# Project-PowerSwitch001.net
KiCad netlist of a schematic drawn in EAGLE
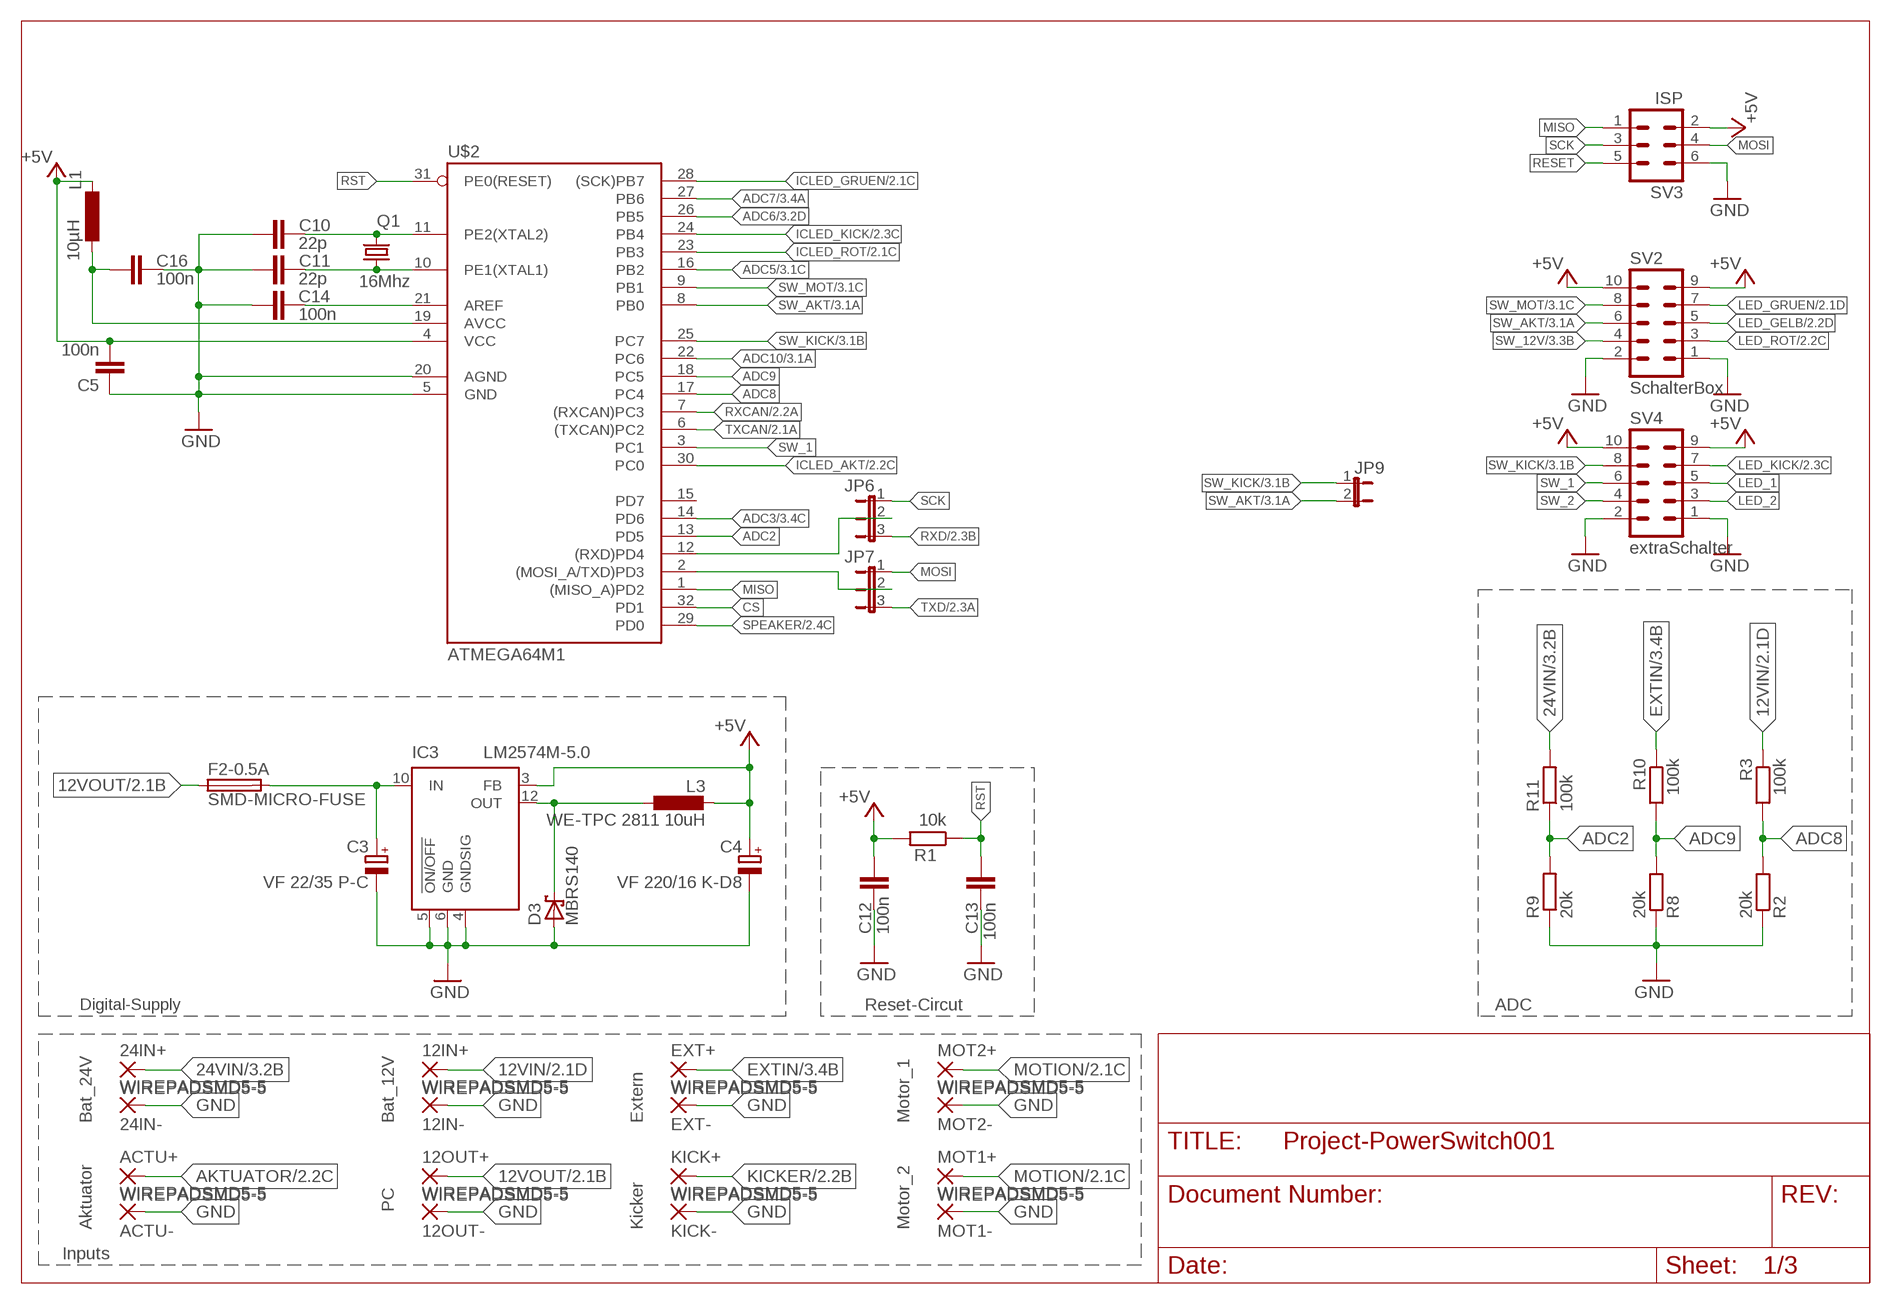
[diagram p0: schematic, sheet 1]
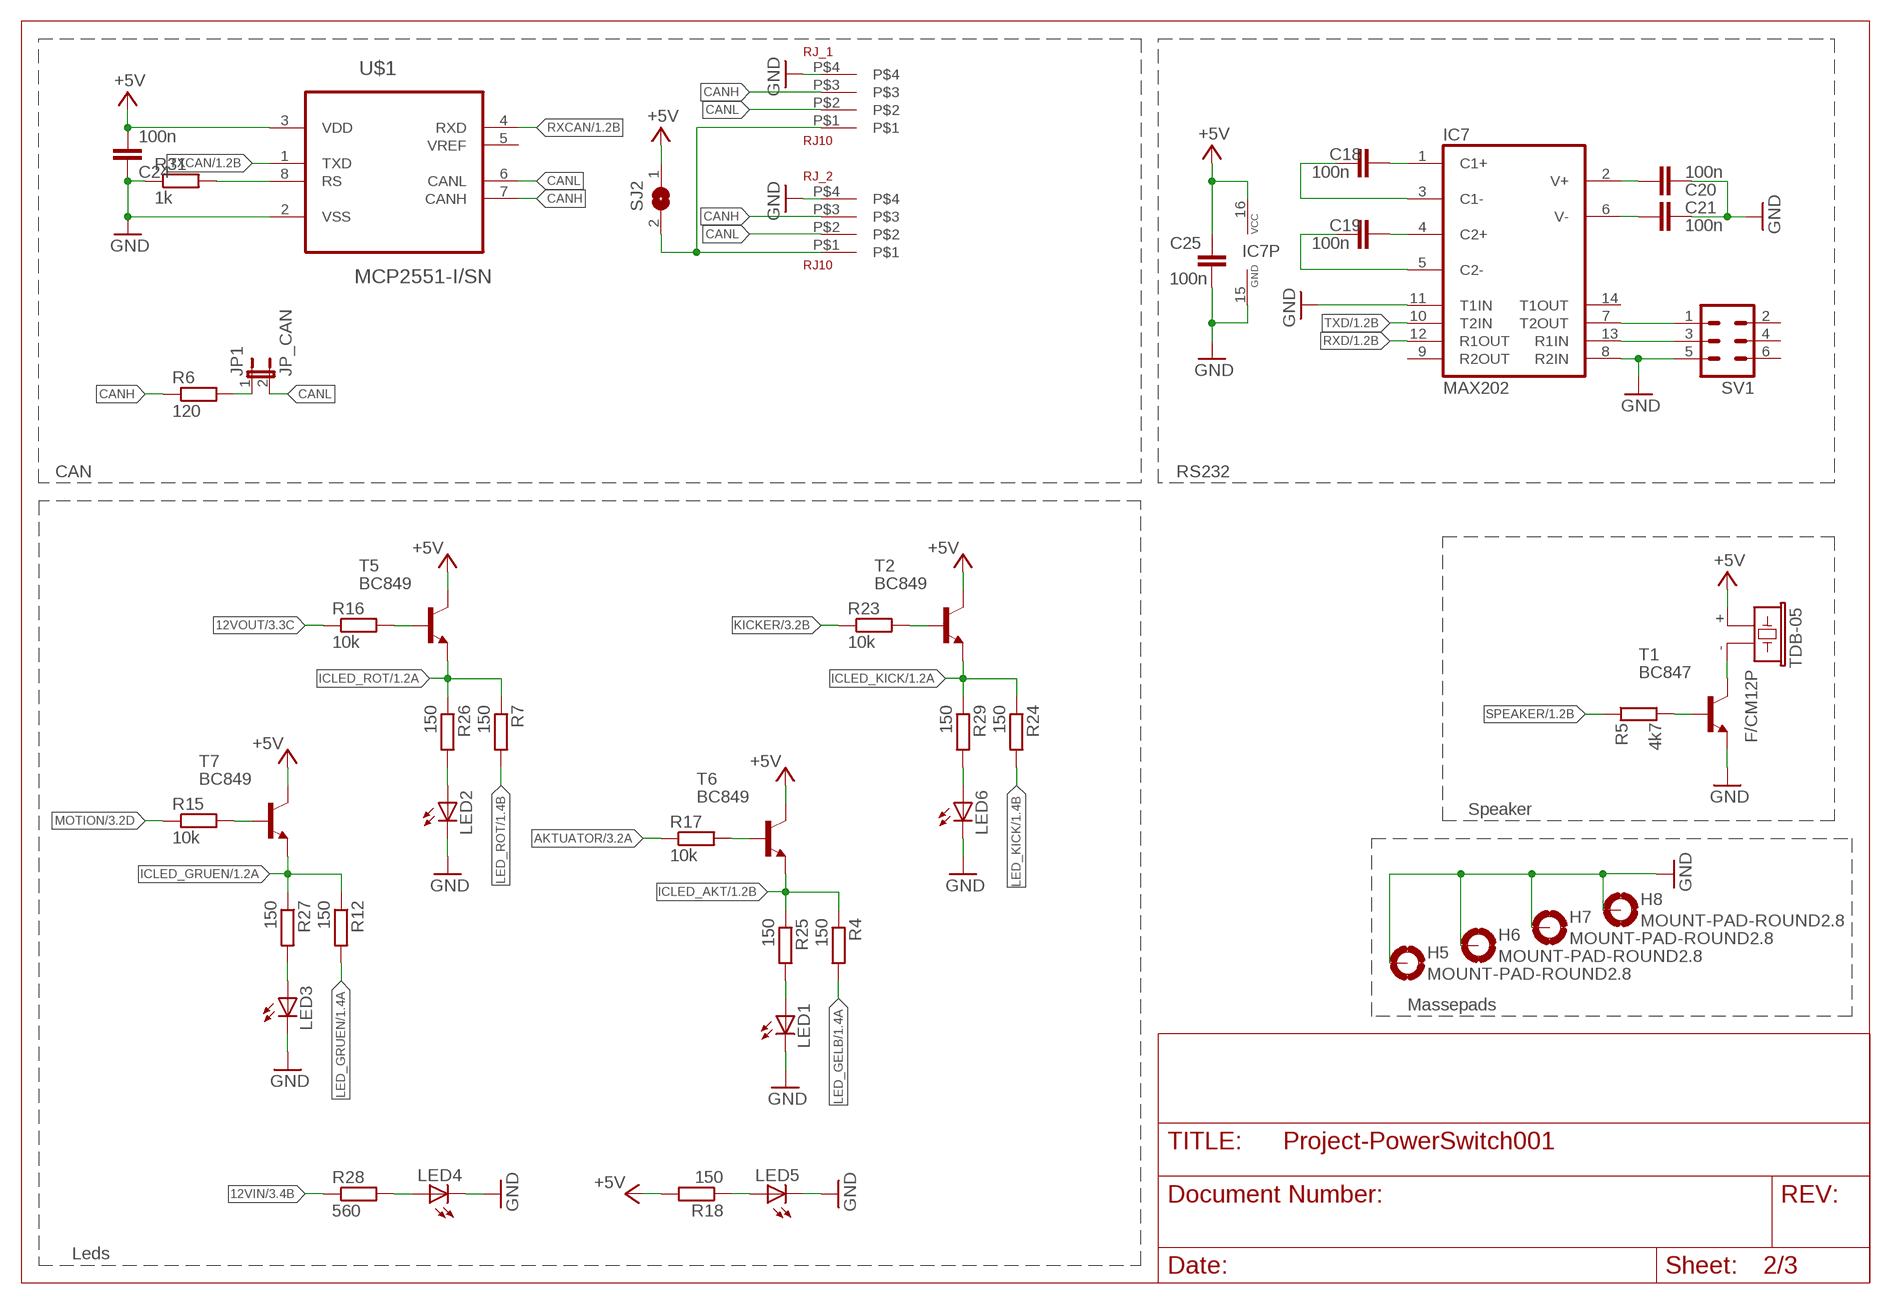
[diagram p1: schematic, sheet 2]
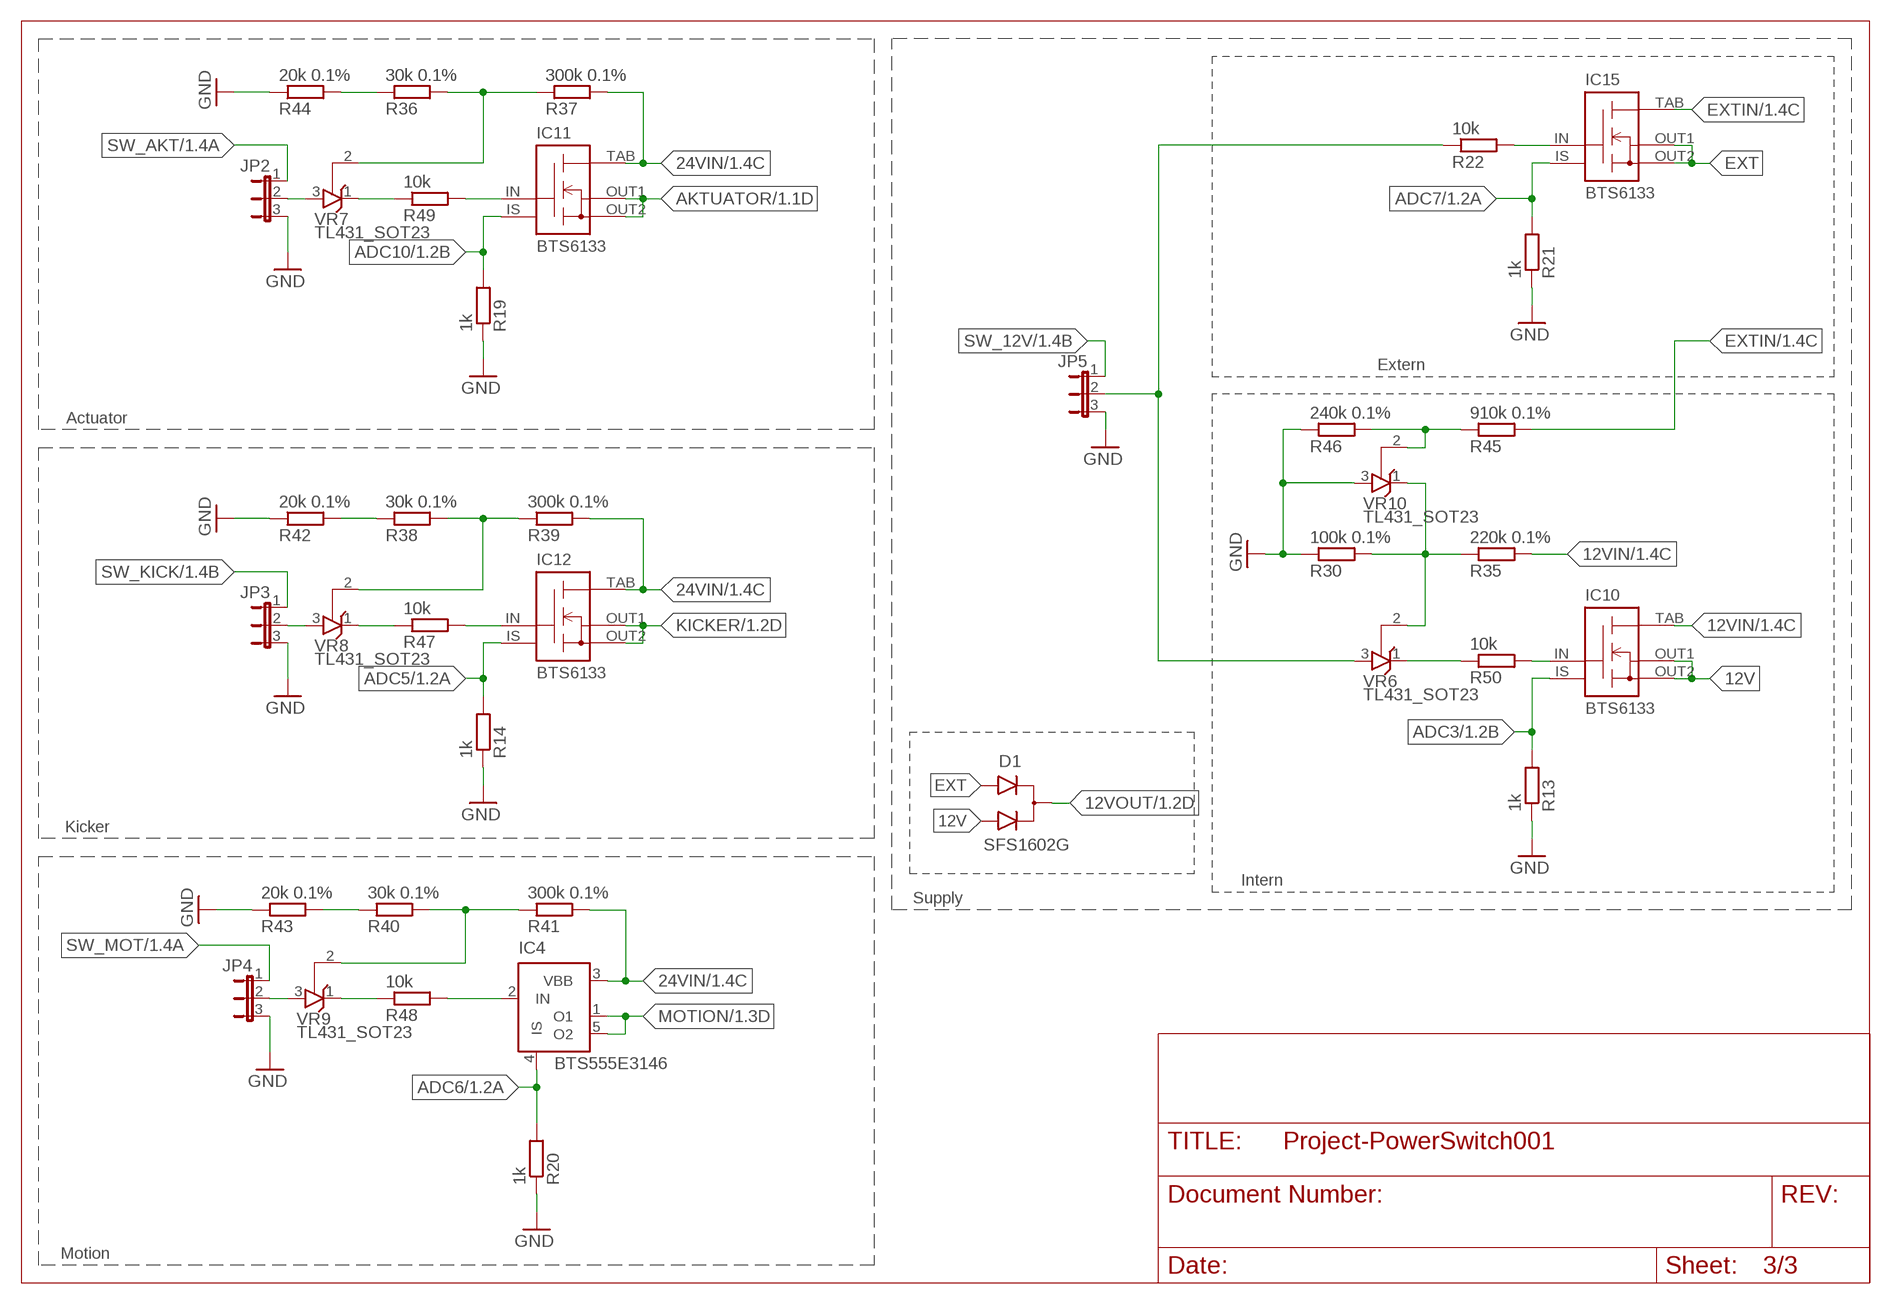
[diagram p2: schematic, sheet 3]

(export (version "E")
  (design (tool "Eeschema 10.0.6"))
  (components
    (comp (ref "C18")
      (value "100n")
      (footprint "eagle-import:C0603K")
      (libsource (lib "eagle-import") (part "C-EUC0603K"))
    )
    (comp (ref "C19")
      (value "100n")
      (footprint "eagle-import:C0603K")
      (libsource (lib "eagle-import") (part "C-EUC0603K"))
    )
    (comp (ref "C20")
      (value "100n")
      (footprint "eagle-import:C0603K")
      (libsource (lib "eagle-import") (part "C-EUC0603K"))
    )
    (comp (ref "C21")
      (value "100n")
      (footprint "eagle-import:C0603K")
      (libsource (lib "eagle-import") (part "C-EUC0603K"))
    )
    (comp (ref "C24")
      (value "100n")
      (footprint "eagle-import:C0603")
      (libsource (lib "eagle-import") (part "C-EUC0603"))
    )
    (comp (ref "C25")
      (value "100n")
      (footprint "eagle-import:C0603K")
      (libsource (lib "eagle-import") (part "C-EUC0603K"))
    )
    (comp (ref "H5")
      (value "MOUNT-PAD-ROUND2.8")
      (footprint "eagle-import:2,8-PAD")
      (libsource (lib "eagle-import") (part "MOUNT-PAD-ROUND2.8"))
    )
    (comp (ref "H6")
      (value "MOUNT-PAD-ROUND2.8")
      (footprint "eagle-import:2,8-PAD")
      (libsource (lib "eagle-import") (part "MOUNT-PAD-ROUND2.8"))
    )
    (comp (ref "H7")
      (value "MOUNT-PAD-ROUND2.8")
      (footprint "eagle-import:2,8-PAD")
      (libsource (lib "eagle-import") (part "MOUNT-PAD-ROUND2.8"))
    )
    (comp (ref "H8")
      (value "MOUNT-PAD-ROUND2.8")
      (footprint "eagle-import:2,8-PAD")
      (libsource (lib "eagle-import") (part "MOUNT-PAD-ROUND2.8"))
    )
    (comp (ref "IC7")
      (value "MAX202")
      (footprint "eagle-import:SO16")
      (fields (field (name "MPN") "MAX3232CSE"))
      (libsource (lib "eagle-import") (part "MAX3232SEC"))
    )
    (comp (ref "JP1")
      (value "JP_CAN")
      (footprint "eagle-import:JP1")
      (libsource (lib "eagle-import") (part "JP1E"))
    )
    (comp (ref "LED1")
      (value "LEDCHIPLED_0805")
      (footprint "eagle-import:CHIPLED_0805")
      (libsource (lib "eagle-import") (part "LEDCHIPLED_0805"))
    )
    (comp (ref "LED2")
      (value "LEDCHIPLED_0805")
      (footprint "eagle-import:CHIPLED_0805")
      (libsource (lib "eagle-import") (part "LEDCHIPLED_0805"))
    )
    (comp (ref "LED3")
      (value "LEDCHIPLED_0805")
      (footprint "eagle-import:CHIPLED_0805")
      (libsource (lib "eagle-import") (part "LEDCHIPLED_0805"))
    )
    (comp (ref "LED4")
      (value "LEDCHIPLED_0805")
      (footprint "eagle-import:CHIPLED_0805")
      (libsource (lib "eagle-import") (part "LEDCHIPLED_0805"))
    )
    (comp (ref "LED5")
      (value "LEDCHIPLED_0805")
      (footprint "eagle-import:CHIPLED_0805")
      (libsource (lib "eagle-import") (part "LEDCHIPLED_0805"))
    )
    (comp (ref "LED6")
      (value "LEDCHIPLED_0805")
      (footprint "eagle-import:CHIPLED_0805")
      (libsource (lib "eagle-import") (part "LEDCHIPLED_0805"))
    )
    (comp (ref "R4")
      (value "150")
      (footprint "eagle-import:R0805")
      (libsource (lib "eagle-import") (part "R-EU_R0805"))
    )
    (comp (ref "R5")
      (value "4k7")
      (footprint "eagle-import:R0805")
      (libsource (lib "eagle-import") (part "R-EU_R0805"))
    )
    (comp (ref "R6")
      (value "120")
      (footprint "eagle-import:M0805")
      (libsource (lib "eagle-import") (part "R-EU_M0805"))
    )
    (comp (ref "R7")
      (value "150")
      (footprint "eagle-import:R0805")
      (libsource (lib "eagle-import") (part "R-EU_R0805"))
    )
    (comp (ref "R12")
      (value "150")
      (footprint "eagle-import:R0805")
      (libsource (lib "eagle-import") (part "R-EU_R0805"))
    )
    (comp (ref "R15")
      (value "10k")
      (footprint "eagle-import:R0805")
      (libsource (lib "eagle-import") (part "R-EU_R0805"))
    )
    (comp (ref "R16")
      (value "10k")
      (footprint "eagle-import:R0805")
      (libsource (lib "eagle-import") (part "R-EU_R0805"))
    )
    (comp (ref "R17")
      (value "10k")
      (footprint "eagle-import:R0805")
      (libsource (lib "eagle-import") (part "R-EU_R0805"))
    )
    (comp (ref "R18")
      (value "150")
      (footprint "eagle-import:R0805")
      (libsource (lib "eagle-import") (part "R-EU_R0805"))
    )
    (comp (ref "R23")
      (value "10k")
      (footprint "eagle-import:R0805")
      (libsource (lib "eagle-import") (part "R-EU_R0805"))
    )
    (comp (ref "R24")
      (value "150")
      (footprint "eagle-import:R0805")
      (libsource (lib "eagle-import") (part "R-EU_R0805"))
    )
    (comp (ref "R25")
      (value "150")
      (footprint "eagle-import:R0805")
      (libsource (lib "eagle-import") (part "R-EU_R0805"))
    )
    (comp (ref "R26")
      (value "150")
      (footprint "eagle-import:R0805")
      (libsource (lib "eagle-import") (part "R-EU_R0805"))
    )
    (comp (ref "R27")
      (value "150")
      (footprint "eagle-import:R0805")
      (libsource (lib "eagle-import") (part "R-EU_R0805"))
    )
    (comp (ref "R28")
      (value "560")
      (footprint "eagle-import:R0805")
      (libsource (lib "eagle-import") (part "R-EU_R0805"))
    )
    (comp (ref "R29")
      (value "150")
      (footprint "eagle-import:R0805")
      (libsource (lib "eagle-import") (part "R-EU_R0805"))
    )
    (comp (ref "R31")
      (value "1k")
      (footprint "eagle-import:R0805")
      (libsource (lib "eagle-import") (part "R-EU_R0805"))
    )
    (comp (ref "RJ_1")
      (value "RJ10")
      (footprint "eagle-import:RJ10")
      (libsource (lib "eagle-import") (part "RJ10"))
    )
    (comp (ref "RJ_2")
      (value "RJ10")
      (footprint "eagle-import:RJ10")
      (libsource (lib "eagle-import") (part "RJ10"))
    )
    (comp (ref "SJ2") (value "SJ") (footprint "eagle-import:SJ") (libsource (lib "eagle-import") (part "SJ")))
    (comp (ref "SV1")
      (value "ML6")
      (footprint "eagle-import:ML6")
      (libsource (lib "eagle-import") (part "ML6"))
    )
    (comp (ref "T1")
      (value "BC847")
      (footprint "eagle-import:SOT23")
      (libsource (lib "eagle-import") (part "BC847"))
    )
    (comp (ref "T2")
      (value "BC849")
      (footprint "eagle-import:SOT23")
      (libsource (lib "eagle-import") (part "BC849"))
    )
    (comp (ref "T5")
      (value "BC849")
      (footprint "eagle-import:SOT23")
      (libsource (lib "eagle-import") (part "BC849"))
    )
    (comp (ref "T6")
      (value "BC849")
      (footprint "eagle-import:SOT23")
      (libsource (lib "eagle-import") (part "BC849"))
    )
    (comp (ref "T7")
      (value "BC849")
      (footprint "eagle-import:SOT23")
      (libsource (lib "eagle-import") (part "BC849"))
    )
    (comp (ref "TDB-05")
      (value "F/CM12P")
      (footprint "eagle-import:F_CM12P")
      (libsource (lib "eagle-import") (part "F/CM12P"))
    )
    (comp (ref "U$1")
      (value "MCP2551-I/SN")
      (footprint "eagle-import:SOIC127P600X175-8N")
      (libsource (lib "eagle-import") (part "MCP2551-I/SN"))
    )
    (comp (ref "12IN+")
      (value "WIREPADSMD5-5")
      (footprint "eagle-import:5-5")
      (libsource (lib "eagle-import") (part "WIREPADSMD5-5"))
    )
    (comp (ref "12IN-")
      (value "WIREPADSMD5-5")
      (footprint "eagle-import:5-5")
      (libsource (lib "eagle-import") (part "WIREPADSMD5-5"))
    )
    (comp (ref "12OUT+")
      (value "WIREPADSMD5-5")
      (footprint "eagle-import:5-5")
      (libsource (lib "eagle-import") (part "WIREPADSMD5-5"))
    )
    (comp (ref "12OUT-")
      (value "WIREPADSMD5-5")
      (footprint "eagle-import:5-5")
      (libsource (lib "eagle-import") (part "WIREPADSMD5-5"))
    )
    (comp (ref "24IN+")
      (value "WIREPADSMD5-5")
      (footprint "eagle-import:5-5")
      (libsource (lib "eagle-import") (part "WIREPADSMD5-5"))
    )
    (comp (ref "24IN-")
      (value "WIREPADSMD5-5")
      (footprint "eagle-import:5-5")
      (libsource (lib "eagle-import") (part "WIREPADSMD5-5"))
    )
    (comp (ref "ACTU+")
      (value "WIREPADSMD5-5")
      (footprint "eagle-import:5-5")
      (libsource (lib "eagle-import") (part "WIREPADSMD5-5"))
    )
    (comp (ref "ACTU-")
      (value "WIREPADSMD5-5")
      (footprint "eagle-import:5-5")
      (libsource (lib "eagle-import") (part "WIREPADSMD5-5"))
    )
    (comp (ref "C3")
      (value "VF 22/35 P-C")
      (footprint "eagle-import:PANASONIC_C")
      (libsource (lib "eagle-import") (part "CPOL-EUC"))
    )
    (comp (ref "C4")
      (value "VF 220/16 K-D8")
      (footprint "eagle-import:PANASONIC_D")
      (libsource (lib "eagle-import") (part "CPOL-EUD"))
    )
    (comp (ref "C5")
      (value "100n")
      (footprint "eagle-import:C0603K")
      (libsource (lib "eagle-import") (part "C-EUC0603K"))
    )
    (comp (ref "C10")
      (value "22p")
      (footprint "eagle-import:C0603K")
      (libsource (lib "eagle-import") (part "C-EUC0603K"))
    )
    (comp (ref "C11")
      (value "22p")
      (footprint "eagle-import:C0603K")
      (libsource (lib "eagle-import") (part "C-EUC0603K"))
    )
    (comp (ref "C12")
      (value "100n")
      (footprint "eagle-import:C0603K")
      (libsource (lib "eagle-import") (part "C-EUC0603K"))
    )
    (comp (ref "C13")
      (value "100n")
      (footprint "eagle-import:C0603K")
      (libsource (lib "eagle-import") (part "C-EUC0603K"))
    )
    (comp (ref "C14")
      (value "100n")
      (footprint "eagle-import:C0603K")
      (libsource (lib "eagle-import") (part "C-EUC0603K"))
    )
    (comp (ref "C16")
      (value "100n")
      (footprint "eagle-import:C0603K")
      (libsource (lib "eagle-import") (part "C-EUC0603K"))
    )
    (comp (ref "D3")
      (value "MBRS140")
      (footprint "eagle-import:SMB")
      (libsource (lib "eagle-import") (part "SCHOTTKY-DIODESMD"))
    )
    (comp (ref "EXT+")
      (value "WIREPADSMD5-5")
      (footprint "eagle-import:5-5")
      (libsource (lib "eagle-import") (part "WIREPADSMD5-5"))
    )
    (comp (ref "EXT-")
      (value "WIREPADSMD5-5")
      (footprint "eagle-import:5-5")
      (libsource (lib "eagle-import") (part "WIREPADSMD5-5"))
    )
    (comp (ref "F2-0.5A")
      (value "SMD-MICRO-FUSE")
      (footprint "eagle-import:SMD-6,1X2,6")
      (libsource (lib "eagle-import") (part "SMD-MICRO-FUSE"))
    )
    (comp (ref "IC3")
      (value "LM2574M-5.0")
      (footprint "eagle-import:SO14W")
      (libsource (lib "eagle-import") (part "LM2574?-M5.0"))
    )
    (comp (ref "JP6")
      (value "JP2E")
      (footprint "eagle-import:JP2")
      (libsource (lib "eagle-import") (part "JP2E"))
    )
    (comp (ref "JP7")
      (value "JP2E")
      (footprint "eagle-import:JP2")
      (libsource (lib "eagle-import") (part "JP2E"))
    )
    (comp (ref "JP9")
      (value "JP1E")
      (footprint "eagle-import:JP1")
      (libsource (lib "eagle-import") (part "JP1E"))
    )
    (comp (ref "KICK+")
      (value "WIREPADSMD5-5")
      (footprint "eagle-import:5-5")
      (libsource (lib "eagle-import") (part "WIREPADSMD5-5"))
    )
    (comp (ref "KICK-")
      (value "WIREPADSMD5-5")
      (footprint "eagle-import:5-5")
      (libsource (lib "eagle-import") (part "WIREPADSMD5-5"))
    )
    (comp (ref "L1")
      (value "10µH")
      (footprint "eagle-import:R0805")
      (libsource (lib "eagle-import") (part "L-EU-0805L0805"))
    )
    (comp (ref "L3")
      (value "WE-TPC 2811 10uH")
      (footprint "eagle-import:POWER-CHOKE_WE-TPC")
      (libsource (lib "eagle-import") (part "L-EUWE-TPC"))
    )
    (comp (ref "MOT1+")
      (value "WIREPADSMD5-5")
      (footprint "eagle-import:5-5")
      (libsource (lib "eagle-import") (part "WIREPADSMD5-5"))
    )
    (comp (ref "MOT1-")
      (value "WIREPADSMD5-5")
      (footprint "eagle-import:5-5")
      (libsource (lib "eagle-import") (part "WIREPADSMD5-5"))
    )
    (comp (ref "MOT2+")
      (value "WIREPADSMD5-5")
      (footprint "eagle-import:5-5")
      (libsource (lib "eagle-import") (part "WIREPADSMD5-5"))
    )
    (comp (ref "MOT2-")
      (value "WIREPADSMD5-5")
      (footprint "eagle-import:5-5")
      (libsource (lib "eagle-import") (part "WIREPADSMD5-5"))
    )
    (comp (ref "Q1")
      (value "16Mhz")
      (footprint "eagle-import:HC49U-V@1")
      (libsource (lib "eagle-import") (part "CRYTALHC49U-V"))
    )
    (comp (ref "R1")
      (value "10k")
      (footprint "eagle-import:R0805")
      (libsource (lib "eagle-import") (part "R-EU_R0805"))
    )
    (comp (ref "R2")
      (value "20k")
      (footprint "eagle-import:R0805")
      (libsource (lib "eagle-import") (part "R-EU_R0805"))
    )
    (comp (ref "R3")
      (value "100k")
      (footprint "eagle-import:R0805")
      (libsource (lib "eagle-import") (part "R-EU_R0805"))
    )
    (comp (ref "R8")
      (value "20k")
      (footprint "eagle-import:R0805")
      (libsource (lib "eagle-import") (part "R-EU_R0805"))
    )
    (comp (ref "R9")
      (value "20k")
      (footprint "eagle-import:R0805")
      (libsource (lib "eagle-import") (part "R-EU_R0805"))
    )
    (comp (ref "R10")
      (value "100k")
      (footprint "eagle-import:R0805")
      (libsource (lib "eagle-import") (part "R-EU_R0805"))
    )
    (comp (ref "R11")
      (value "100k")
      (footprint "eagle-import:R0805")
      (libsource (lib "eagle-import") (part "R-EU_R0805"))
    )
    (comp (ref "SV2")
      (value "SchalterBox")
      (footprint "eagle-import:ML10")
      (libsource (lib "eagle-import") (part "ML10"))
    )
    (comp (ref "SV3")
      (value "ISP")
      (footprint "eagle-import:ML6")
      (libsource (lib "eagle-import") (part "ML6"))
    )
    (comp (ref "SV4")
      (value "extraSchalter")
      (footprint "eagle-import:ML10")
      (libsource (lib "eagle-import") (part "ML10"))
    )
    (comp (ref "U$2")
      (value "ATMEGA64M1")
      (footprint "eagle-import:TQFP32-08")
      (libsource (lib "eagle-import") (part "ATMEGA64M1"))
    )
    (comp (ref "D1")
      (value "SFS1602G")
      (footprint "eagle-import:D2PAK")
      (libsource (lib "eagle-import") (part "SFS160G"))
    )
    (comp (ref "IC4")
      (value "BTS555E3146")
      (footprint "eagle-import:TO220-52")
      (libsource (lib "eagle-import") (part "BTS555E3146"))
    )
    (comp (ref "IC10")
      (value "BTS6133")
      (footprint "eagle-import:TO252-51")
      (libsource (lib "eagle-import") (part "BTS6133"))
    )
    (comp (ref "IC11")
      (value "BTS6133")
      (footprint "eagle-import:TO252-51")
      (libsource (lib "eagle-import") (part "BTS6133"))
    )
    (comp (ref "IC12")
      (value "BTS6133")
      (footprint "eagle-import:TO252-51")
      (libsource (lib "eagle-import") (part "BTS6133"))
    )
    (comp (ref "IC15")
      (value "BTS6133")
      (footprint "eagle-import:TO252-51")
      (libsource (lib "eagle-import") (part "BTS6133"))
    )
    (comp (ref "JP2")
      (value "JP2E")
      (footprint "eagle-import:JP2")
      (libsource (lib "eagle-import") (part "JP2E"))
    )
    (comp (ref "JP3")
      (value "JP2E")
      (footprint "eagle-import:JP2")
      (libsource (lib "eagle-import") (part "JP2E"))
    )
    (comp (ref "JP4")
      (value "JP2E")
      (footprint "eagle-import:JP2")
      (libsource (lib "eagle-import") (part "JP2E"))
    )
    (comp (ref "JP5")
      (value "JP2E")
      (footprint "eagle-import:JP2")
      (libsource (lib "eagle-import") (part "JP2E"))
    )
    (comp (ref "R13")
      (value "1k")
      (footprint "eagle-import:R0805")
      (libsource (lib "eagle-import") (part "R-EU_R0805"))
    )
    (comp (ref "R14")
      (value "1k")
      (footprint "eagle-import:R0805")
      (libsource (lib "eagle-import") (part "R-EU_R0805"))
    )
    (comp (ref "R19")
      (value "1k")
      (footprint "eagle-import:R0805")
      (libsource (lib "eagle-import") (part "R-EU_R0805"))
    )
    (comp (ref "R20")
      (value "1k")
      (footprint "eagle-import:R0805")
      (libsource (lib "eagle-import") (part "R-EU_R0805"))
    )
    (comp (ref "R21")
      (value "1k")
      (footprint "eagle-import:R0805")
      (libsource (lib "eagle-import") (part "R-EU_R0805"))
    )
    (comp (ref "R22")
      (value "10k")
      (footprint "eagle-import:R0805")
      (libsource (lib "eagle-import") (part "R-EU_R0805"))
    )
    (comp (ref "R30")
      (value "100k 0.1%")
      (footprint "eagle-import:R0805")
      (libsource (lib "eagle-import") (part "R-EU_R0805"))
    )
    (comp (ref "R35")
      (value "220k 0.1%")
      (footprint "eagle-import:R0805")
      (libsource (lib "eagle-import") (part "R-EU_R0805"))
    )
    (comp (ref "R36")
      (value "30k 0.1%")
      (footprint "eagle-import:R0805")
      (libsource (lib "eagle-import") (part "R-EU_R0805"))
    )
    (comp (ref "R37")
      (value "300k 0.1%")
      (footprint "eagle-import:R0805")
      (libsource (lib "eagle-import") (part "R-EU_R0805"))
    )
    (comp (ref "R38")
      (value "30k 0.1%")
      (footprint "eagle-import:R0805")
      (libsource (lib "eagle-import") (part "R-EU_R0805"))
    )
    (comp (ref "R39")
      (value "300k 0.1%")
      (footprint "eagle-import:R0805")
      (libsource (lib "eagle-import") (part "R-EU_R0805"))
    )
    (comp (ref "R40")
      (value "30k 0.1%")
      (footprint "eagle-import:R0805")
      (libsource (lib "eagle-import") (part "R-EU_R0805"))
    )
    (comp (ref "R41")
      (value "300k 0.1%")
      (footprint "eagle-import:R0805")
      (libsource (lib "eagle-import") (part "R-EU_R0805"))
    )
    (comp (ref "R42")
      (value "20k 0.1%")
      (footprint "eagle-import:R0805")
      (libsource (lib "eagle-import") (part "R-EU_R0805"))
    )
    (comp (ref "R43")
      (value "20k 0.1%")
      (footprint "eagle-import:R0805")
      (libsource (lib "eagle-import") (part "R-EU_R0805"))
    )
    (comp (ref "R44")
      (value "20k 0.1%")
      (footprint "eagle-import:R0805")
      (libsource (lib "eagle-import") (part "R-EU_R0805"))
    )
    (comp (ref "R45")
      (value "910k 0.1%")
      (footprint "eagle-import:R0805")
      (libsource (lib "eagle-import") (part "R-EU_R0805"))
    )
    (comp (ref "R46")
      (value "240k 0.1%")
      (footprint "eagle-import:R0805")
      (libsource (lib "eagle-import") (part "R-EU_R0805"))
    )
    (comp (ref "R47")
      (value "10k")
      (footprint "eagle-import:R0805")
      (libsource (lib "eagle-import") (part "R-EU_R0805"))
    )
    (comp (ref "R48")
      (value "10k")
      (footprint "eagle-import:R0805")
      (libsource (lib "eagle-import") (part "R-EU_R0805"))
    )
    (comp (ref "R49")
      (value "10k")
      (footprint "eagle-import:R0805")
      (libsource (lib "eagle-import") (part "R-EU_R0805"))
    )
    (comp (ref "R50")
      (value "10k")
      (footprint "eagle-import:R0805")
      (libsource (lib "eagle-import") (part "R-EU_R0805"))
    )
    (comp (ref "VR6")
      (value "TL431_SOT23")
      (footprint "eagle-import:SOT23")
      (libsource (lib "eagle-import") (part "TL431_SOT23"))
    )
    (comp (ref "VR7")
      (value "TL431_SOT23")
      (footprint "eagle-import:SOT23")
      (libsource (lib "eagle-import") (part "TL431_SOT23"))
    )
    (comp (ref "VR8")
      (value "TL431_SOT23")
      (footprint "eagle-import:SOT23")
      (libsource (lib "eagle-import") (part "TL431_SOT23"))
    )
    (comp (ref "VR9")
      (value "TL431_SOT23")
      (footprint "eagle-import:SOT23")
      (libsource (lib "eagle-import") (part "TL431_SOT23"))
    )
    (comp (ref "VR10")
      (value "TL431_SOT23")
      (footprint "eagle-import:SOT23")
      (libsource (lib "eagle-import") (part "TL431_SOT23"))
    )
  )
  (nets
    (net (code "1") (name "+5V") (class "Default")
      (node (ref "C12") (pin "2") (pinfunction "2_2") (pintype "passive"))
      (node (ref "C24") (pin "2") (pinfunction "2_2") (pintype "passive"))
      (node (ref "C25") (pin "1") (pinfunction "1_1") (pintype "passive"))
      (node (ref "C4") (pin "+") (pinfunction "+_+") (pintype "passive"))
      (node (ref "C5") (pin "2") (pinfunction "2_2") (pintype "passive"))
      (node (ref "IC3") (pin "3") (pinfunction "FB_3") (pintype "input"))
      (node (ref "IC7") (pin "16") (pinfunction "VCC_16") (pintype "power_in"))
      (node (ref "L1") (pin "2") (pinfunction "2_2") (pintype "passive"))
      (node (ref "L3") (pin "2") (pinfunction "2_2") (pintype "passive"))
      (node (ref "R1") (pin "2") (pinfunction "2_2") (pintype "passive"))
      (node (ref "R18") (pin "2") (pinfunction "2_2") (pintype "passive"))
      (node (ref "SJ2") (pin "1") (pinfunction "1_1") (pintype "passive"))
      (node (ref "SV2") (pin "10") (pinfunction "10_10") (pintype "passive"))
      (node (ref "SV2") (pin "9") (pinfunction "9_9") (pintype "passive"))
      (node (ref "SV3") (pin "2") (pinfunction "2_2") (pintype "passive"))
      (node (ref "SV4") (pin "10") (pinfunction "10_10") (pintype "passive"))
      (node (ref "SV4") (pin "9") (pinfunction "9_9") (pintype "passive"))
      (node (ref "T2") (pin "3") (pinfunction "C_3") (pintype "passive"))
      (node (ref "T5") (pin "3") (pinfunction "C_3") (pintype "passive"))
      (node (ref "T6") (pin "3") (pinfunction "C_3") (pintype "passive"))
      (node (ref "T7") (pin "3") (pinfunction "C_3") (pintype "passive"))
      (node (ref "TDB-05") (pin "+") (pinfunction "1_+") (pintype "passive"))
      (node (ref "U$1") (pin "3") (pinfunction "VDD_3") (pintype "power_in"))
      (node (ref "U$2") (pin "4") (pinfunction "VCC_4") (pintype "bidirectional"))
    )
    (net (code "2") (name "12V") (class "Default")
      (node (ref "D1") (pin "P$2") (pinfunction "P$2_P$2") (pintype "bidirectional"))
      (node (ref "IC10") (pin "OUT1") (pinfunction "OUT_OUT1") (pintype "passive"))
      (node (ref "IC10") (pin "OUT2") (pinfunction "OUT_OUT2") (pintype "passive"))
    )
    (net (code "3") (name "12VIN") (class "Default")
      (node (ref "12IN+") (pin "P$1") (pinfunction "P_P$1") (pintype "passive"))
      (node (ref "IC10") (pin "TAB") (pinfunction "VBB_TAB") (pintype "power_in"))
      (node (ref "R28") (pin "1") (pinfunction "1_1") (pintype "passive"))
      (node (ref "R3") (pin "1") (pinfunction "1_1") (pintype "passive"))
      (node (ref "R35") (pin "2") (pinfunction "2_2") (pintype "passive"))
    )
    (net (code "4") (name "12VOUT") (class "Default")
      (node (ref "12OUT+") (pin "P$1") (pinfunction "P_P$1") (pintype "passive"))
      (node (ref "D1") (pin "P$3") (pinfunction "P$3_P$3") (pintype "bidirectional"))
      (node (ref "F2-0.5A") (pin "1") (pinfunction "1_1") (pintype "passive"))
      (node (ref "R16") (pin "1") (pinfunction "1_1") (pintype "passive"))
    )
    (net (code "5") (name "24VIN") (class "Default")
      (node (ref "24IN+") (pin "P$1") (pinfunction "P_P$1") (pintype "passive"))
      (node (ref "IC11") (pin "TAB") (pinfunction "VBB_TAB") (pintype "power_in"))
      (node (ref "IC12") (pin "TAB") (pinfunction "VBB_TAB") (pintype "power_in"))
      (node (ref "IC4") (pin "3") (pinfunction "VBB_3") (pintype "passive"))
      (node (ref "R11") (pin "2") (pinfunction "2_2") (pintype "passive"))
      (node (ref "R37") (pin "2") (pinfunction "2_2") (pintype "passive"))
      (node (ref "R39") (pin "2") (pinfunction "2_2") (pintype "passive"))
      (node (ref "R41") (pin "2") (pinfunction "2_2") (pintype "passive"))
    )
    (net (code "6") (name "ADC2") (class "Default")
      (node (ref "R11") (pin "1") (pinfunction "1_1") (pintype "passive"))
      (node (ref "R9") (pin "2") (pinfunction "2_2") (pintype "passive"))
      (node (ref "U$2") (pin "13") (pinfunction "PD5_13") (pintype "bidirectional"))
    )
    (net (code "7") (name "ADC3") (class "Default")
      (node (ref "IC10") (pin "IS") (pinfunction "IS_IS") (pintype "passive"))
      (node (ref "R13") (pin "2") (pinfunction "2_2") (pintype "passive"))
      (node (ref "U$2") (pin "14") (pinfunction "PD6_14") (pintype "bidirectional"))
    )
    (net (code "8") (name "ADC5") (class "Default")
      (node (ref "IC12") (pin "IS") (pinfunction "IS_IS") (pintype "passive"))
      (node (ref "R14") (pin "2") (pinfunction "2_2") (pintype "passive"))
      (node (ref "U$2") (pin "16") (pinfunction "PB2_16") (pintype "bidirectional"))
    )
    (net (code "9") (name "ADC6") (class "Default")
      (node (ref "IC4") (pin "4") (pinfunction "IS_4") (pintype "passive"))
      (node (ref "R20") (pin "2") (pinfunction "2_2") (pintype "passive"))
      (node (ref "U$2") (pin "26") (pinfunction "PB5_26") (pintype "bidirectional"))
    )
    (net (code "10") (name "ADC7") (class "Default")
      (node (ref "IC15") (pin "IS") (pinfunction "IS_IS") (pintype "passive"))
      (node (ref "R21") (pin "2") (pinfunction "2_2") (pintype "passive"))
      (node (ref "U$2") (pin "27") (pinfunction "PB6_27") (pintype "bidirectional"))
    )
    (net (code "11") (name "ADC8") (class "Default")
      (node (ref "R2") (pin "2") (pinfunction "2_2") (pintype "passive"))
      (node (ref "R3") (pin "2") (pinfunction "2_2") (pintype "passive"))
      (node (ref "U$2") (pin "17") (pinfunction "PC4_17") (pintype "bidirectional"))
    )
    (net (code "12") (name "ADC9") (class "Default")
      (node (ref "R10") (pin "2") (pinfunction "2_2") (pintype "passive"))
      (node (ref "R8") (pin "2") (pinfunction "2_2") (pintype "passive"))
      (node (ref "U$2") (pin "18") (pinfunction "PC5_18") (pintype "bidirectional"))
    )
    (net (code "13") (name "ADC10") (class "Default")
      (node (ref "IC11") (pin "IS") (pinfunction "IS_IS") (pintype "passive"))
      (node (ref "R19") (pin "2") (pinfunction "2_2") (pintype "passive"))
      (node (ref "U$2") (pin "22") (pinfunction "PC6_22") (pintype "bidirectional"))
    )
    (net (code "14") (name "AKTUATOR") (class "Default")
      (node (ref "ACTU+") (pin "P$1") (pinfunction "P_P$1") (pintype "passive"))
      (node (ref "IC11") (pin "OUT1") (pinfunction "OUT_OUT1") (pintype "passive"))
      (node (ref "IC11") (pin "OUT2") (pinfunction "OUT_OUT2") (pintype "passive"))
      (node (ref "R17") (pin "1") (pinfunction "1_1") (pintype "passive"))
    )
    (net (code "15") (name "CANH") (class "Default")
      (node (ref "R6") (pin "1") (pinfunction "1_1") (pintype "passive"))
      (node (ref "RJ_1") (pin "P$3") (pinfunction "P$3_P$3") (pintype "bidirectional"))
      (node (ref "RJ_2") (pin "P$3") (pinfunction "P$3_P$3") (pintype "bidirectional"))
      (node (ref "U$1") (pin "7") (pinfunction "CANH_7") (pintype "bidirectional"))
    )
    (net (code "16") (name "CANL") (class "Default")
      (node (ref "JP1") (pin "2") (pinfunction "2_2") (pintype "passive"))
      (node (ref "RJ_1") (pin "P$2") (pinfunction "P$2_P$2") (pintype "bidirectional"))
      (node (ref "RJ_2") (pin "P$2") (pinfunction "P$2_P$2") (pintype "bidirectional"))
      (node (ref "U$1") (pin "6") (pinfunction "CANL_6") (pintype "bidirectional"))
    )
    (net (code "17") (name "CS") (class "Default")
      (node (ref "U$2") (pin "32") (pinfunction "PD1_32") (pintype "bidirectional"))
    )
    (net (code "18") (name "EXT") (class "Default")
      (node (ref "D1") (pin "P$1") (pinfunction "P$1_P$1") (pintype "bidirectional"))
      (node (ref "IC15") (pin "OUT1") (pinfunction "OUT_OUT1") (pintype "passive"))
      (node (ref "IC15") (pin "OUT2") (pinfunction "OUT_OUT2") (pintype "passive"))
    )
    (net (code "19") (name "EXTIN") (class "Default")
      (node (ref "EXT+") (pin "P$1") (pinfunction "P_P$1") (pintype "passive"))
      (node (ref "IC15") (pin "TAB") (pinfunction "VBB_TAB") (pintype "power_in"))
      (node (ref "R10") (pin "1") (pinfunction "1_1") (pintype "passive"))
      (node (ref "R45") (pin "2") (pinfunction "2_2") (pintype "passive"))
    )
    (net (code "20") (name "GND") (class "Default")
      (node (ref "12IN-") (pin "P$1") (pinfunction "P_P$1") (pintype "passive"))
      (node (ref "12OUT-") (pin "P$1") (pinfunction "P_P$1") (pintype "passive"))
      (node (ref "24IN-") (pin "P$1") (pinfunction "P_P$1") (pintype "passive"))
      (node (ref "ACTU-") (pin "P$1") (pinfunction "P_P$1") (pintype "passive"))
      (node (ref "C10") (pin "1") (pinfunction "1_1") (pintype "passive"))
      (node (ref "C11") (pin "1") (pinfunction "1_1") (pintype "passive"))
      (node (ref "C12") (pin "1") (pinfunction "1_1") (pintype "passive"))
      (node (ref "C13") (pin "1") (pinfunction "1_1") (pintype "passive"))
      (node (ref "C14") (pin "1") (pinfunction "1_1") (pintype "passive"))
      (node (ref "C16") (pin "2") (pinfunction "2_2") (pintype "passive"))
      (node (ref "C20") (pin "2") (pinfunction "2_2") (pintype "passive"))
      (node (ref "C21") (pin "2") (pinfunction "2_2") (pintype "passive"))
      (node (ref "C24") (pin "1") (pinfunction "1_1") (pintype "passive"))
      (node (ref "C25") (pin "2") (pinfunction "2_2") (pintype "passive"))
      (node (ref "C3") (pin "-") (pinfunction "-_-") (pintype "passive"))
      (node (ref "C4") (pin "-") (pinfunction "-_-") (pintype "passive"))
      (node (ref "C5") (pin "1") (pinfunction "1_1") (pintype "passive"))
      (node (ref "D3") (pin "A") (pinfunction "A_A") (pintype "passive"))
      (node (ref "EXT-") (pin "P$1") (pinfunction "P_P$1") (pintype "passive"))
      (node (ref "H5") (pin "B2,8") (pinfunction "MOUNT_B2,8") (pintype "passive"))
      (node (ref "H6") (pin "B2,8") (pinfunction "MOUNT_B2,8") (pintype "passive"))
      (node (ref "H7") (pin "B2,8") (pinfunction "MOUNT_B2,8") (pintype "passive"))
      (node (ref "H8") (pin "B2,8") (pinfunction "MOUNT_B2,8") (pintype "passive"))
      (node (ref "IC3") (pin "4") (pinfunction "GNDSIG_4") (pintype "input"))
      (node (ref "IC3") (pin "5") (pinfunction "~{ON/OFF}_5") (pintype "input"))
      (node (ref "IC3") (pin "6") (pinfunction "GND_6") (pintype "power_in"))
      (node (ref "IC7") (pin "11") (pinfunction "T1IN_11") (pintype "input"))
      (node (ref "IC7") (pin "15") (pinfunction "GND_15") (pintype "power_in"))
      (node (ref "IC7") (pin "8") (pinfunction "R2IN_8") (pintype "input"))
      (node (ref "JP2") (pin "3") (pinfunction "3_3") (pintype "passive"))
      (node (ref "JP3") (pin "3") (pinfunction "3_3") (pintype "passive"))
      (node (ref "JP4") (pin "3") (pinfunction "3_3") (pintype "passive"))
      (node (ref "JP5") (pin "3") (pinfunction "3_3") (pintype "passive"))
      (node (ref "KICK-") (pin "P$1") (pinfunction "P_P$1") (pintype "passive"))
      (node (ref "LED1") (pin "C") (pinfunction "C_C") (pintype "passive"))
      (node (ref "LED2") (pin "C") (pinfunction "C_C") (pintype "passive"))
      (node (ref "LED3") (pin "C") (pinfunction "C_C") (pintype "passive"))
      (node (ref "LED4") (pin "C") (pinfunction "C_C") (pintype "passive"))
      (node (ref "LED5") (pin "C") (pinfunction "C_C") (pintype "passive"))
      (node (ref "LED6") (pin "C") (pinfunction "C_C") (pintype "passive"))
      (node (ref "MOT1-") (pin "P$1") (pinfunction "P_P$1") (pintype "passive"))
      (node (ref "MOT2-") (pin "P$1") (pinfunction "P_P$1") (pintype "passive"))
      (node (ref "R13") (pin "1") (pinfunction "1_1") (pintype "passive"))
      (node (ref "R14") (pin "1") (pinfunction "1_1") (pintype "passive"))
      (node (ref "R19") (pin "1") (pinfunction "1_1") (pintype "passive"))
      (node (ref "R2") (pin "1") (pinfunction "1_1") (pintype "passive"))
      (node (ref "R20") (pin "1") (pinfunction "1_1") (pintype "passive"))
      (node (ref "R21") (pin "1") (pinfunction "1_1") (pintype "passive"))
      (node (ref "R30") (pin "1") (pinfunction "1_1") (pintype "passive"))
      (node (ref "R31") (pin "1") (pinfunction "1_1") (pintype "passive"))
      (node (ref "R42") (pin "1") (pinfunction "1_1") (pintype "passive"))
      (node (ref "R43") (pin "1") (pinfunction "1_1") (pintype "passive"))
      (node (ref "R44") (pin "1") (pinfunction "1_1") (pintype "passive"))
      (node (ref "R46") (pin "1") (pinfunction "1_1") (pintype "passive"))
      (node (ref "R8") (pin "1") (pinfunction "1_1") (pintype "passive"))
      (node (ref "R9") (pin "1") (pinfunction "1_1") (pintype "passive"))
      (node (ref "RJ_1") (pin "P$4") (pinfunction "P$4_P$4") (pintype "bidirectional"))
      (node (ref "RJ_2") (pin "P$4") (pinfunction "P$4_P$4") (pintype "bidirectional"))
      (node (ref "SV1") (pin "5") (pinfunction "5_5") (pintype "passive"))
      (node (ref "SV2") (pin "1") (pinfunction "1_1") (pintype "passive"))
      (node (ref "SV2") (pin "2") (pinfunction "2_2") (pintype "passive"))
      (node (ref "SV3") (pin "6") (pinfunction "6_6") (pintype "passive"))
      (node (ref "SV4") (pin "1") (pinfunction "1_1") (pintype "passive"))
      (node (ref "SV4") (pin "2") (pinfunction "2_2") (pintype "passive"))
      (node (ref "T1") (pin "2") (pinfunction "E_2") (pintype "passive"))
      (node (ref "U$1") (pin "2") (pinfunction "VSS_2") (pintype "passive"))
      (node (ref "U$2") (pin "20") (pinfunction "AGND_20") (pintype "power_in"))
      (node (ref "U$2") (pin "5") (pinfunction "GND_5") (pintype "power_in"))
      (node (ref "VR10") (pin "3") (pinfunction "A_3") (pintype "passive"))
    )
    (net (code "21") (name "ICLED_AKT") (class "Default")
      (node (ref "R25") (pin "1") (pinfunction "1_1") (pintype "passive"))
      (node (ref "R4") (pin "1") (pinfunction "1_1") (pintype "passive"))
      (node (ref "T6") (pin "2") (pinfunction "E_2") (pintype "passive"))
      (node (ref "U$2") (pin "30") (pinfunction "PC0_30") (pintype "bidirectional"))
    )
    (net (code "22") (name "ICLED_GRUEN") (class "Default")
      (node (ref "R12") (pin "1") (pinfunction "1_1") (pintype "passive"))
      (node (ref "R27") (pin "1") (pinfunction "1_1") (pintype "passive"))
      (node (ref "T7") (pin "2") (pinfunction "E_2") (pintype "passive"))
      (node (ref "U$2") (pin "28") (pinfunction "(SCK)PB7_28") (pintype "bidirectional"))
    )
    (net (code "23") (name "ICLED_KICK") (class "Default")
      (node (ref "R24") (pin "1") (pinfunction "1_1") (pintype "passive"))
      (node (ref "R29") (pin "1") (pinfunction "1_1") (pintype "passive"))
      (node (ref "T2") (pin "2") (pinfunction "E_2") (pintype "passive"))
      (node (ref "U$2") (pin "24") (pinfunction "PB4_24") (pintype "bidirectional"))
    )
    (net (code "24") (name "ICLED_ROT") (class "Default")
      (node (ref "R26") (pin "1") (pinfunction "1_1") (pintype "passive"))
      (node (ref "R7") (pin "1") (pinfunction "1_1") (pintype "passive"))
      (node (ref "T5") (pin "2") (pinfunction "E_2") (pintype "passive"))
      (node (ref "U$2") (pin "23") (pinfunction "PB3_23") (pintype "bidirectional"))
    )
    (net (code "25") (name "KICKER") (class "Default")
      (node (ref "IC12") (pin "OUT1") (pinfunction "OUT_OUT1") (pintype "passive"))
      (node (ref "IC12") (pin "OUT2") (pinfunction "OUT_OUT2") (pintype "passive"))
      (node (ref "KICK+") (pin "P$1") (pinfunction "P_P$1") (pintype "passive"))
      (node (ref "R23") (pin "1") (pinfunction "1_1") (pintype "passive"))
    )
    (net (code "26") (name "LED_1") (class "Default")
      (node (ref "SV4") (pin "5") (pinfunction "5_5") (pintype "passive"))
    )
    (net (code "27") (name "LED_2") (class "Default")
      (node (ref "SV4") (pin "3") (pinfunction "3_3") (pintype "passive"))
    )
    (net (code "28") (name "LED_GELB") (class "Default")
      (node (ref "R4") (pin "2") (pinfunction "2_2") (pintype "passive"))
      (node (ref "SV2") (pin "5") (pinfunction "5_5") (pintype "passive"))
    )
    (net (code "29") (name "LED_GRUEN") (class "Default")
      (node (ref "R12") (pin "2") (pinfunction "2_2") (pintype "passive"))
      (node (ref "SV2") (pin "7") (pinfunction "7_7") (pintype "passive"))
    )
    (net (code "30") (name "LED_KICK") (class "Default")
      (node (ref "R24") (pin "2") (pinfunction "2_2") (pintype "passive"))
      (node (ref "SV4") (pin "7") (pinfunction "7_7") (pintype "passive"))
    )
    (net (code "31") (name "LED_ROT") (class "Default")
      (node (ref "R7") (pin "2") (pinfunction "2_2") (pintype "passive"))
      (node (ref "SV2") (pin "3") (pinfunction "3_3") (pintype "passive"))
    )
    (net (code "32") (name "MISO") (class "Default")
      (node (ref "SV3") (pin "1") (pinfunction "1_1") (pintype "passive"))
      (node (ref "U$2") (pin "1") (pinfunction "(MISO_A)PD2_1") (pintype "bidirectional"))
    )
    (net (code "33") (name "MOSI") (class "Default")
      (node (ref "JP7") (pin "1") (pinfunction "1_1") (pintype "passive"))
      (node (ref "SV3") (pin "4") (pinfunction "4_4") (pintype "passive"))
    )
    (net (code "34") (name "MOTION") (class "Default")
      (node (ref "IC4") (pin "1") (pinfunction "O1_1") (pintype "passive"))
      (node (ref "IC4") (pin "5") (pinfunction "O2_5") (pintype "passive"))
      (node (ref "MOT1+") (pin "P$1") (pinfunction "P_P$1") (pintype "passive"))
      (node (ref "MOT2+") (pin "P$1") (pinfunction "P_P$1") (pintype "passive"))
      (node (ref "R15") (pin "1") (pinfunction "1_1") (pintype "passive"))
    )
    (net (code "35") (name "Net-(IC3-IN)") (class "Default")
      (node (ref "C3") (pin "+") (pinfunction "+_+") (pintype "passive"))
      (node (ref "F2-0.5A") (pin "2") (pinfunction "2_2") (pintype "passive"))
      (node (ref "IC3") (pin "10") (pinfunction "IN_10") (pintype "input"))
    )
    (net (code "36") (name "Net-(IC3-OUT)") (class "Default")
      (node (ref "D3") (pin "C") (pinfunction "C_C") (pintype "passive"))
      (node (ref "IC3") (pin "12") (pinfunction "OUT_12") (pintype "passive"))
      (node (ref "L3") (pin "1") (pinfunction "1_1") (pintype "passive"))
    )
    (net (code "37") (name "Net-(IC4-IN)") (class "Default")
      (node (ref "IC4") (pin "2") (pinfunction "IN_2") (pintype "input"))
      (node (ref "R48") (pin "2") (pinfunction "2_2") (pintype "passive"))
    )
    (net (code "38") (name "Net-(IC7A-C1+)") (class "Default")
      (node (ref "C18") (pin "2") (pinfunction "2_2") (pintype "passive"))
      (node (ref "IC7") (pin "1") (pinfunction "C1+_1") (pintype "bidirectional"))
    )
    (net (code "39") (name "Net-(IC7A-C1-)") (class "Default")
      (node (ref "C18") (pin "1") (pinfunction "1_1") (pintype "passive"))
      (node (ref "IC7") (pin "3") (pinfunction "C1-_3") (pintype "bidirectional"))
    )
    (net (code "40") (name "Net-(IC7A-C2+)") (class "Default")
      (node (ref "C19") (pin "2") (pinfunction "2_2") (pintype "passive"))
      (node (ref "IC7") (pin "4") (pinfunction "C2+_4") (pintype "bidirectional"))
    )
    (net (code "41") (name "Net-(IC7A-C2-)") (class "Default")
      (node (ref "C19") (pin "1") (pinfunction "1_1") (pintype "passive"))
      (node (ref "IC7") (pin "5") (pinfunction "C2-_5") (pintype "bidirectional"))
    )
    (net (code "42") (name "Net-(IC7A-R1IN)") (class "Default")
      (node (ref "IC7") (pin "13") (pinfunction "R1IN_13") (pintype "input"))
      (node (ref "SV1") (pin "3") (pinfunction "3_3") (pintype "passive"))
    )
    (net (code "43") (name "Net-(IC7A-T2OUT)") (class "Default")
      (node (ref "IC7") (pin "7") (pinfunction "T2OUT_7") (pintype "output"))
      (node (ref "SV1") (pin "1") (pinfunction "1_1") (pintype "passive"))
    )
    (net (code "44") (name "Net-(IC7A-V+)") (class "Default")
      (node (ref "C20") (pin "1") (pinfunction "1_1") (pintype "passive"))
      (node (ref "IC7") (pin "2") (pinfunction "V+_2") (pintype "bidirectional"))
    )
    (net (code "45") (name "Net-(IC7A-V-)") (class "Default")
      (node (ref "C21") (pin "1") (pinfunction "1_1") (pintype "passive"))
      (node (ref "IC7") (pin "6") (pinfunction "V-_6") (pintype "bidirectional"))
    )
    (net (code "46") (name "Net-(IC10-PadIN)") (class "Default")
      (node (ref "IC10") (pin "IN") (pinfunction "IN_IN") (pintype "input"))
      (node (ref "R50") (pin "2") (pinfunction "2_2") (pintype "passive"))
    )
    (net (code "47") (name "Net-(IC11-PadIN)") (class "Default")
      (node (ref "IC11") (pin "IN") (pinfunction "IN_IN") (pintype "input"))
      (node (ref "R49") (pin "2") (pinfunction "2_2") (pintype "passive"))
    )
    (net (code "48") (name "Net-(IC12-PadIN)") (class "Default")
      (node (ref "IC12") (pin "IN") (pinfunction "IN_IN") (pintype "input"))
      (node (ref "R47") (pin "2") (pinfunction "2_2") (pintype "passive"))
    )
    (net (code "49") (name "Net-(IC15-PadIN)") (class "Default")
      (node (ref "IC15") (pin "IN") (pinfunction "IN_IN") (pintype "input"))
      (node (ref "R22") (pin "2") (pinfunction "2_2") (pintype "passive"))
    )
    (net (code "50") (name "Net-(JP1-Pad1)") (class "Default")
      (node (ref "JP1") (pin "1") (pinfunction "1_1") (pintype "passive"))
      (node (ref "R6") (pin "2") (pinfunction "2_2") (pintype "passive"))
    )
    (net (code "51") (name "Net-(LED1-PadA)") (class "Default")
      (node (ref "LED1") (pin "A") (pinfunction "A_A") (pintype "passive"))
      (node (ref "R25") (pin "2") (pinfunction "2_2") (pintype "passive"))
    )
    (net (code "52") (name "Net-(LED2-PadA)") (class "Default")
      (node (ref "LED2") (pin "A") (pinfunction "A_A") (pintype "passive"))
      (node (ref "R26") (pin "2") (pinfunction "2_2") (pintype "passive"))
    )
    (net (code "53") (name "Net-(LED3-PadA)") (class "Default")
      (node (ref "LED3") (pin "A") (pinfunction "A_A") (pintype "passive"))
      (node (ref "R27") (pin "2") (pinfunction "2_2") (pintype "passive"))
    )
    (net (code "54") (name "Net-(LED4-PadA)") (class "Default")
      (node (ref "LED4") (pin "A") (pinfunction "A_A") (pintype "passive"))
      (node (ref "R28") (pin "2") (pinfunction "2_2") (pintype "passive"))
    )
    (net (code "55") (name "Net-(LED5-PadA)") (class "Default")
      (node (ref "LED5") (pin "A") (pinfunction "A_A") (pintype "passive"))
      (node (ref "R18") (pin "1") (pinfunction "1_1") (pintype "passive"))
    )
    (net (code "56") (name "Net-(LED6-PadA)") (class "Default")
      (node (ref "LED6") (pin "A") (pinfunction "A_A") (pintype "passive"))
      (node (ref "R29") (pin "2") (pinfunction "2_2") (pintype "passive"))
    )
    (net (code "57") (name "Net-(R36-Pad1)") (class "Default")
      (node (ref "R36") (pin "1") (pinfunction "1_1") (pintype "passive"))
      (node (ref "R44") (pin "2") (pinfunction "2_2") (pintype "passive"))
    )
    (net (code "58") (name "Net-(R38-Pad1)") (class "Default")
      (node (ref "R38") (pin "1") (pinfunction "1_1") (pintype "passive"))
      (node (ref "R42") (pin "2") (pinfunction "2_2") (pintype "passive"))
    )
    (net (code "59") (name "Net-(R40-Pad1)") (class "Default")
      (node (ref "R40") (pin "1") (pinfunction "1_1") (pintype "passive"))
      (node (ref "R43") (pin "2") (pinfunction "2_2") (pintype "passive"))
    )
    (net (code "60") (name "Net-(RJ_1-PadP$1)") (class "Default")
      (node (ref "RJ_1") (pin "P$1") (pinfunction "P$1_P$1") (pintype "bidirectional"))
      (node (ref "RJ_2") (pin "P$1") (pinfunction "P$1_P$1") (pintype "bidirectional"))
      (node (ref "SJ2") (pin "2") (pinfunction "2_2") (pintype "passive"))
    )
    (net (code "61") (name "Net-(T1-B)") (class "Default")
      (node (ref "R5") (pin "2") (pinfunction "2_2") (pintype "passive"))
      (node (ref "T1") (pin "1") (pinfunction "B_1") (pintype "passive"))
    )
    (net (code "62") (name "Net-(T1-C)") (class "Default")
      (node (ref "T1") (pin "3") (pinfunction "C_3") (pintype "passive"))
      (node (ref "TDB-05") (pin "-") (pinfunction "2_-") (pintype "passive"))
    )
    (net (code "63") (name "Net-(T2-B)") (class "Default")
      (node (ref "R23") (pin "2") (pinfunction "2_2") (pintype "passive"))
      (node (ref "T2") (pin "1") (pinfunction "B_1") (pintype "passive"))
    )
    (net (code "64") (name "Net-(T5-B)") (class "Default")
      (node (ref "R16") (pin "2") (pinfunction "2_2") (pintype "passive"))
      (node (ref "T5") (pin "1") (pinfunction "B_1") (pintype "passive"))
    )
    (net (code "65") (name "Net-(T6-B)") (class "Default")
      (node (ref "R17") (pin "2") (pinfunction "2_2") (pintype "passive"))
      (node (ref "T6") (pin "1") (pinfunction "B_1") (pintype "passive"))
    )
    (net (code "66") (name "Net-(T7-B)") (class "Default")
      (node (ref "R15") (pin "2") (pinfunction "2_2") (pintype "passive"))
      (node (ref "T7") (pin "1") (pinfunction "B_1") (pintype "passive"))
    )
    (net (code "67") (name "Net-(U$1-RS)") (class "Default")
      (node (ref "R31") (pin "2") (pinfunction "2_2") (pintype "passive"))
      (node (ref "U$1") (pin "8") (pinfunction "RS_8") (pintype "input"))
    )
    (net (code "68") (name "Net-(U$2-(MOSI_A{slash}TXD)PD3)") (class "Default")
      (node (ref "JP7") (pin "2") (pinfunction "2_2") (pintype "passive"))
      (node (ref "U$2") (pin "2") (pinfunction "(MOSI_A/TXD)PD3_2") (pintype "bidirectional"))
    )
    (net (code "69") (name "Net-(U$2-(RXD)PD4)") (class "Default")
      (node (ref "JP6") (pin "2") (pinfunction "2_2") (pintype "passive"))
      (node (ref "U$2") (pin "12") (pinfunction "(RXD)PD4_12") (pintype "bidirectional"))
    )
    (net (code "70") (name "Net-(U$2-AREF)") (class "Default")
      (node (ref "C14") (pin "2") (pinfunction "2_2") (pintype "passive"))
      (node (ref "U$2") (pin "21") (pinfunction "AREF_21") (pintype "bidirectional"))
    )
    (net (code "71") (name "Net-(U$2-AVCC)") (class "Default")
      (node (ref "C16") (pin "1") (pinfunction "1_1") (pintype "passive"))
      (node (ref "L1") (pin "1") (pinfunction "1_1") (pintype "passive"))
      (node (ref "U$2") (pin "19") (pinfunction "AVCC_19") (pintype "bidirectional"))
    )
    (net (code "72") (name "Net-(U$2-PE1(XTAL1))") (class "Default")
      (node (ref "C11") (pin "2") (pinfunction "2_2") (pintype "passive"))
      (node (ref "Q1") (pin "1") (pinfunction "1_1") (pintype "passive"))
      (node (ref "U$2") (pin "10") (pinfunction "PE1(XTAL1)_10") (pintype "bidirectional"))
    )
    (net (code "73") (name "Net-(U$2-PE2(XTAL2))") (class "Default")
      (node (ref "C10") (pin "2") (pinfunction "2_2") (pintype "passive"))
      (node (ref "Q1") (pin "2") (pinfunction "2_2") (pintype "passive"))
      (node (ref "U$2") (pin "11") (pinfunction "PE2(XTAL2)_11") (pintype "bidirectional"))
    )
    (net (code "74") (name "Net-(VR6-A)") (class "Default")
      (node (ref "JP5") (pin "2") (pinfunction "2_2") (pintype "passive"))
      (node (ref "R22") (pin "1") (pinfunction "1_1") (pintype "passive"))
      (node (ref "VR6") (pin "3") (pinfunction "A_3") (pintype "passive"))
    )
    (net (code "75") (name "Net-(VR6-C)") (class "Default")
      (node (ref "R50") (pin "1") (pinfunction "1_1") (pintype "passive"))
      (node (ref "VR6") (pin "1") (pinfunction "C_1") (pintype "passive"))
    )
    (net (code "76") (name "Net-(VR7-A)") (class "Default")
      (node (ref "JP2") (pin "2") (pinfunction "2_2") (pintype "passive"))
      (node (ref "VR7") (pin "3") (pinfunction "A_3") (pintype "passive"))
    )
    (net (code "77") (name "Net-(VR7-C)") (class "Default")
      (node (ref "R49") (pin "1") (pinfunction "1_1") (pintype "passive"))
      (node (ref "VR7") (pin "1") (pinfunction "C_1") (pintype "passive"))
    )
    (net (code "78") (name "Net-(VR7-R)") (class "Default")
      (node (ref "R36") (pin "2") (pinfunction "2_2") (pintype "passive"))
      (node (ref "R37") (pin "1") (pinfunction "1_1") (pintype "passive"))
      (node (ref "VR7") (pin "2") (pinfunction "R_2") (pintype "passive"))
    )
    (net (code "79") (name "Net-(VR8-A)") (class "Default")
      (node (ref "JP3") (pin "2") (pinfunction "2_2") (pintype "passive"))
      (node (ref "VR8") (pin "3") (pinfunction "A_3") (pintype "passive"))
    )
    (net (code "80") (name "Net-(VR8-C)") (class "Default")
      (node (ref "R47") (pin "1") (pinfunction "1_1") (pintype "passive"))
      (node (ref "VR8") (pin "1") (pinfunction "C_1") (pintype "passive"))
    )
    (net (code "81") (name "Net-(VR8-R)") (class "Default")
      (node (ref "R38") (pin "2") (pinfunction "2_2") (pintype "passive"))
      (node (ref "R39") (pin "1") (pinfunction "1_1") (pintype "passive"))
      (node (ref "VR8") (pin "2") (pinfunction "R_2") (pintype "passive"))
    )
    (net (code "82") (name "Net-(VR9-A)") (class "Default")
      (node (ref "JP4") (pin "2") (pinfunction "2_2") (pintype "passive"))
      (node (ref "VR9") (pin "3") (pinfunction "A_3") (pintype "passive"))
    )
    (net (code "83") (name "Net-(VR9-C)") (class "Default")
      (node (ref "R48") (pin "1") (pinfunction "1_1") (pintype "passive"))
      (node (ref "VR9") (pin "1") (pinfunction "C_1") (pintype "passive"))
    )
    (net (code "84") (name "Net-(VR9-R)") (class "Default")
      (node (ref "R40") (pin "2") (pinfunction "2_2") (pintype "passive"))
      (node (ref "R41") (pin "1") (pinfunction "1_1") (pintype "passive"))
      (node (ref "VR9") (pin "2") (pinfunction "R_2") (pintype "passive"))
    )
    (net (code "85") (name "Net-(VR10-C)") (class "Default")
      (node (ref "R30") (pin "2") (pinfunction "2_2") (pintype "passive"))
      (node (ref "R35") (pin "1") (pinfunction "1_1") (pintype "passive"))
      (node (ref "VR10") (pin "1") (pinfunction "C_1") (pintype "passive"))
      (node (ref "VR6") (pin "2") (pinfunction "R_2") (pintype "passive"))
    )
    (net (code "86") (name "Net-(VR10-R)") (class "Default")
      (node (ref "R45") (pin "1") (pinfunction "1_1") (pintype "passive"))
      (node (ref "R46") (pin "2") (pinfunction "2_2") (pintype "passive"))
      (node (ref "VR10") (pin "2") (pinfunction "R_2") (pintype "passive"))
    )
    (net (code "87") (name "RESET") (class "Default")
      (node (ref "SV3") (pin "5") (pinfunction "5_5") (pintype "passive"))
    )
    (net (code "88") (name "RST") (class "Default")
      (node (ref "C13") (pin "2") (pinfunction "2_2") (pintype "passive"))
      (node (ref "R1") (pin "1") (pinfunction "1_1") (pintype "passive"))
      (node (ref "U$2") (pin "31") (pinfunction "PE0(RESET)_31") (pintype "input"))
    )
    (net (code "89") (name "RXCAN") (class "Default")
      (node (ref "U$1") (pin "4") (pinfunction "RXD_4") (pintype "output"))
      (node (ref "U$2") (pin "7") (pinfunction "(RXCAN)PC3_7") (pintype "bidirectional"))
    )
    (net (code "90") (name "RXD") (class "Default")
      (node (ref "IC7") (pin "12") (pinfunction "R1OUT_12") (pintype "output"))
      (node (ref "JP6") (pin "3") (pinfunction "3_3") (pintype "passive"))
    )
    (net (code "91") (name "SCK") (class "Default")
      (node (ref "JP6") (pin "1") (pinfunction "1_1") (pintype "passive"))
      (node (ref "SV3") (pin "3") (pinfunction "3_3") (pintype "passive"))
    )
    (net (code "92") (name "SPEAKER") (class "Default")
      (node (ref "R5") (pin "1") (pinfunction "1_1") (pintype "passive"))
      (node (ref "U$2") (pin "29") (pinfunction "PD0_29") (pintype "bidirectional"))
    )
    (net (code "93") (name "SW_1") (class "Default")
      (node (ref "SV4") (pin "6") (pinfunction "6_6") (pintype "passive"))
      (node (ref "U$2") (pin "3") (pinfunction "PC1_3") (pintype "bidirectional"))
    )
    (net (code "94") (name "SW_2") (class "Default")
      (node (ref "SV4") (pin "4") (pinfunction "4_4") (pintype "passive"))
    )
    (net (code "95") (name "SW_12V") (class "Default")
      (node (ref "JP5") (pin "1") (pinfunction "1_1") (pintype "passive"))
      (node (ref "SV2") (pin "4") (pinfunction "4_4") (pintype "passive"))
    )
    (net (code "96") (name "SW_AKT") (class "Default")
      (node (ref "JP2") (pin "1") (pinfunction "1_1") (pintype "passive"))
      (node (ref "JP9") (pin "2") (pinfunction "2_2") (pintype "passive"))
      (node (ref "SV2") (pin "6") (pinfunction "6_6") (pintype "passive"))
      (node (ref "U$2") (pin "8") (pinfunction "PB0_8") (pintype "bidirectional"))
    )
    (net (code "97") (name "SW_KICK") (class "Default")
      (node (ref "JP3") (pin "1") (pinfunction "1_1") (pintype "passive"))
      (node (ref "JP9") (pin "1") (pinfunction "1_1") (pintype "passive"))
      (node (ref "SV4") (pin "8") (pinfunction "8_8") (pintype "passive"))
      (node (ref "U$2") (pin "25") (pinfunction "PC7_25") (pintype "bidirectional"))
    )
    (net (code "98") (name "SW_MOT") (class "Default")
      (node (ref "JP4") (pin "1") (pinfunction "1_1") (pintype "passive"))
      (node (ref "SV2") (pin "8") (pinfunction "8_8") (pintype "passive"))
      (node (ref "U$2") (pin "9") (pinfunction "PB1_9") (pintype "bidirectional"))
    )
    (net (code "99") (name "TXCAN") (class "Default")
      (node (ref "U$1") (pin "1") (pinfunction "TXD_1") (pintype "input"))
      (node (ref "U$2") (pin "6") (pinfunction "(TXCAN)PC2_6") (pintype "bidirectional"))
    )
    (net (code "100") (name "TXD") (class "Default")
      (node (ref "IC7") (pin "10") (pinfunction "T2IN_10") (pintype "input"))
      (node (ref "JP7") (pin "3") (pinfunction "3_3") (pintype "passive"))
    )
    (net (code "101") (name "unconnected-(IC7A-R2OUT-Pad9)") (class "Default")
      (node (ref "IC7") (pin "9") (pinfunction "R2OUT_9") (pintype "output"))
    )
    (net (code "102") (name "unconnected-(IC7A-T1OUT-Pad14)") (class "Default")
      (node (ref "IC7") (pin "14") (pinfunction "T1OUT_14") (pintype "output"))
    )
    (net (code "103") (name "unconnected-(SV1-Pad2)") (class "Default")
      (node (ref "SV1") (pin "2") (pinfunction "2_2") (pintype "passive"))
    )
    (net (code "104") (name "unconnected-(SV1-Pad4)") (class "Default")
      (node (ref "SV1") (pin "4") (pinfunction "4_4") (pintype "passive"))
    )
    (net (code "105") (name "unconnected-(SV1-Pad6)") (class "Default")
      (node (ref "SV1") (pin "6") (pinfunction "6_6") (pintype "passive"))
    )
    (net (code "106") (name "unconnected-(U$1-VREF-Pad5)") (class "Default")
      (node (ref "U$1") (pin "5") (pinfunction "VREF_5") (pintype "output"))
    )
    (net (code "107") (name "unconnected-(U$2-PD7-Pad15)") (class "Default")
      (node (ref "U$2") (pin "15") (pinfunction "PD7_15") (pintype "bidirectional"))
    )
  )
)
